# ip_phone_e_wifi.net
KiCad netlist of a schematic drawn in Altium Designer
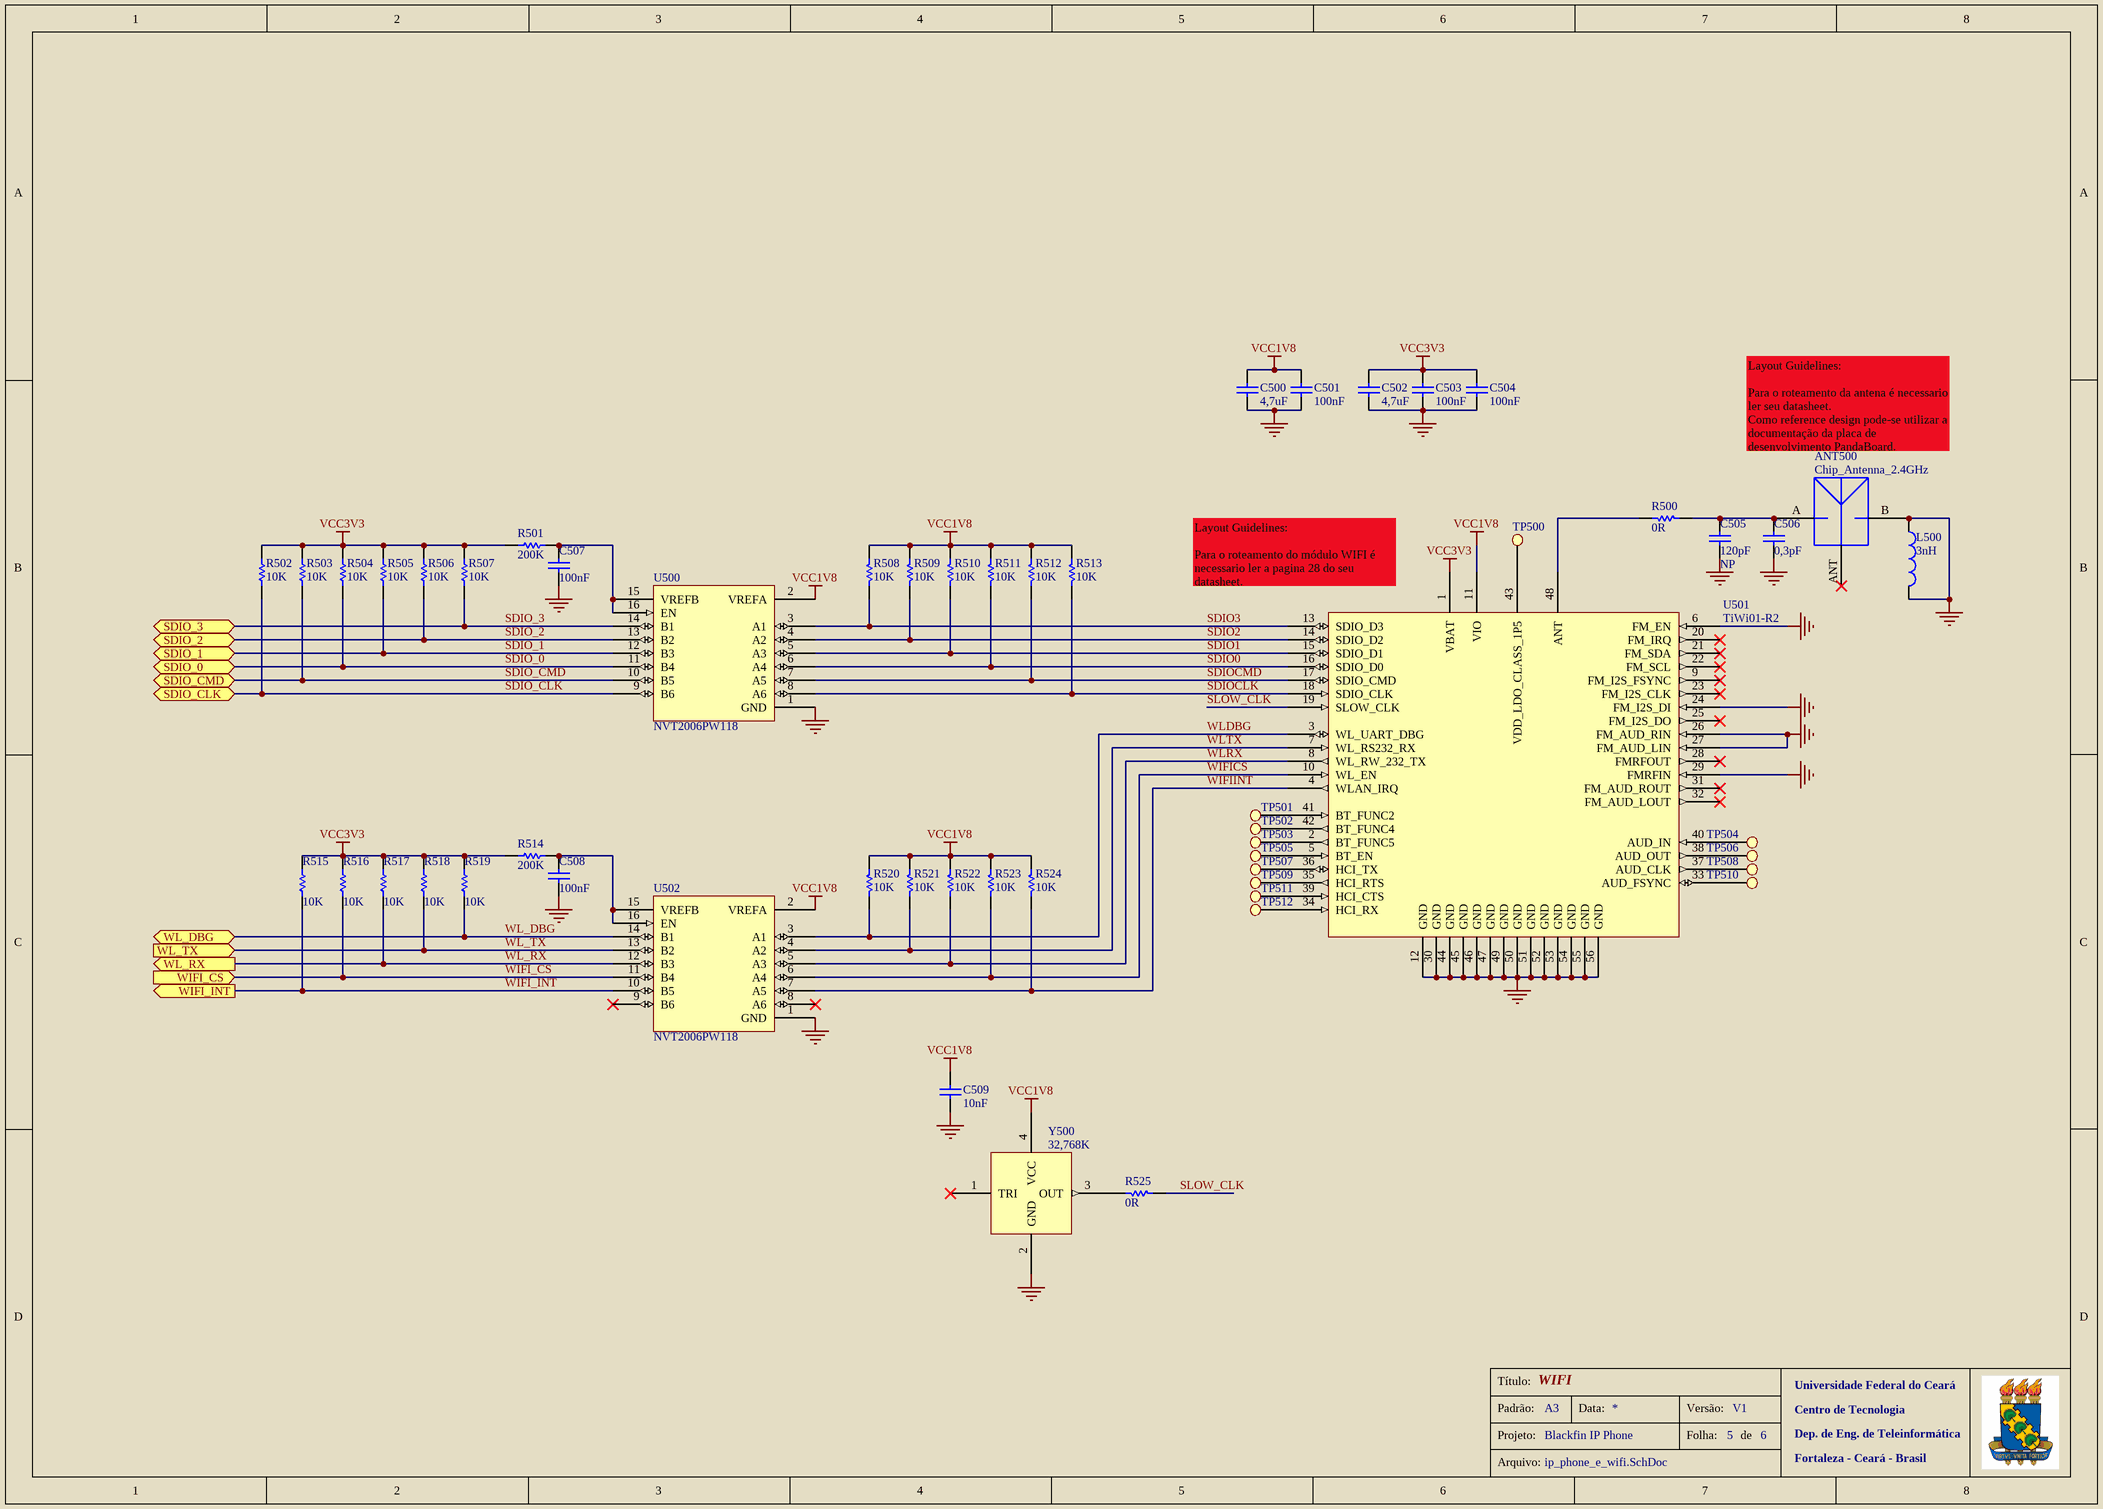
[diagram p0: ip_phone_e_wifi.SchDoc]

(export (version "E")
  (design (tool "Eeschema 10.0.6"))
  (components
    (comp (ref "ANT500")
      (value "Chip_Antenna_2.4GHz")
      (footprint "ip_phone:ANTENNA")
      (description "Antenna 2.4GHz Ceramic Chip SMD")
      (fields (field (name "MANUFACTURER") "TDK") (field (name "EVENDORPART#") "445-6134-1-ND"))
      (libsource (lib "ip_phone") (part "Antenna2_4GHzChip"))
    )
    (comp (ref "C500")
      (value "4,7uF")
      (footprint "ip_phone:CC1005-0402")
      (description "MLCC - SMD/SMT 4.7uF 20% 6.3Volts 0402")
      (fields (field (name "EVENDORPART#") "810-C1005X5R0J475M") (field (name "MANUFACTURER") "TDK"))
      (libsource (lib "ip_phone") (part "Capacitor"))
    )
    (comp (ref "C501")
      (value "100nF")
      (footprint "ip_phone:CC1005-0402")
      (description "MLCC - SMD/SMT 0.1UF 16V 10% 0402")
      (fields (field (name "EVENDORPART#") "810-C1005X7R1C104K") (field (name "MANUFACTURER") "TDK"))
      (libsource (lib "ip_phone") (part "Capacitor"))
    )
    (comp (ref "C502")
      (value "4,7uF")
      (footprint "ip_phone:CC1005-0402")
      (description "MLCC - SMD/SMT 4.7uF 20% 6.3Volts 0402")
      (fields (field (name "EVENDORPART#") "810-C1005X5R0J475M") (field (name "MANUFACTURER") "TDK"))
      (libsource (lib "ip_phone") (part "Capacitor"))
    )
    (comp (ref "C503")
      (value "100nF")
      (footprint "ip_phone:CC1005-0402")
      (description "MLCC - SMD/SMT 0.1UF 16V 10% 0402")
      (fields (field (name "EVENDORPART#") "810-C1005X7R1C104K") (field (name "MANUFACTURER") "TDK"))
      (libsource (lib "ip_phone") (part "Capacitor"))
    )
    (comp (ref "C504")
      (value "100nF")
      (footprint "ip_phone:CC1005-0402")
      (description "MLCC - SMD/SMT 0.1UF 16V 10% 0402")
      (fields (field (name "EVENDORPART#") "810-C1005X7R1C104K") (field (name "MANUFACTURER") "TDK"))
      (libsource (lib "ip_phone") (part "Capacitor"))
    )
    (comp (ref "C505")
      (value "120pF")
      (footprint "ip_phone:CC1005-0402_NP")
      (description "MLCC - SMD/SMT 0402 120pF 50volts C0G 5%")
      (fields
        (field (name "EVENDORPART#") "810-C1005C0G1H121J")
        (field (name "MANUFACTURER") "TDK")
        (field (name "NP") "NP")
      )
      (libsource (lib "ip_phone") (part "Capacitor"))
    )
    (comp (ref "C506")
      (value "0,3pF")
      (footprint "ip_phone:CC1005-0402")
      (description "MLCC - SMD/SMT 0.3pF 50Volts C0G 0.1pF")
      (fields (field (name "EVENDORPART#") "81-GRM1535C1HR30BD5D") (field (name "MANUFACTURER") "Murata"))
      (libsource (lib "ip_phone") (part "Capacitor"))
    )
    (comp (ref "C507")
      (value "100nF")
      (footprint "ip_phone:CC1005-0402")
      (description "MLCC - SMD/SMT 0.1UF 16V 10% 0402")
      (fields (field (name "EVENDORPART#") "810-C1005X7R1C104K") (field (name "MANUFACTURER") "TDK"))
      (libsource (lib "ip_phone") (part "Capacitor"))
    )
    (comp (ref "C508")
      (value "100nF")
      (footprint "ip_phone:CC1005-0402")
      (description "MLCC - SMD/SMT 0.1UF 16V 10% 0402")
      (fields (field (name "EVENDORPART#") "810-C1005X7R1C104K") (field (name "MANUFACTURER") "TDK"))
      (libsource (lib "ip_phone") (part "Capacitor"))
    )
    (comp (ref "C509")
      (value "10nF")
      (footprint "ip_phone:CC1005-0402")
      (description "Ceramic Capacitor 10nF 50V X7R 0402")
      (fields (field (name "EVENDORPART#") "810-C1005X7R1C103K") (field (name "MANUFACTURER") "TDK"))
      (libsource (lib "ip_phone") (part "Capacitor"))
    )
    (comp (ref "L500")
      (value "3nH")
      (footprint "ip_phone:INDUTOR_0402")
      (description "Inductor")
      (fields
        (field (name "EVENDORPART#") "712-1457-1-ND")
        (field (name "MANUFACTURER") "Johanson Technology Inc")
      )
      (libsource (lib "ip_phone") (part "Inductor"))
    )
    (comp (ref "R500")
      (value "0R")
      (footprint "ip_phone:CR1005-0402")
      (description "Thick Film Resistors 0402 1/16W Jumper")
      (fields
        (field (name "EVENDORPART#") "667-ERJ-2GE0R00X")
        (field (name "MANUFACTURER") "Panasonic Electronic Components")
      )
      (libsource (lib "ip_phone") (part "Resistor"))
    )
    (comp (ref "R501")
      (value "200K")
      (footprint "ip_phone:CR1005-0402")
      (description "Thick Film Resistors 1/16WATT 200K 0402")
      (fields (field (name "EVENDORPART#") "304-200K-RC") (field (name "MANUFACTURER") "Xicon"))
      (libsource (lib "ip_phone") (part "Resistor"))
    )
    (comp (ref "R502")
      (value "10K")
      (footprint "ip_phone:CR1005-0402")
      (description "Thick Film Resistors SMD 0402 10K 5%  1/16 W")
      (fields (field (name "EVENDORPART#") "311-10KJRCT-ND") (field (name "MANUFACTURER") "Yageo"))
      (libsource (lib "ip_phone") (part "Resistor"))
    )
    (comp (ref "R503")
      (value "10K")
      (footprint "ip_phone:CR1005-0402")
      (description "Thick Film Resistors SMD 0402 10K 5%  1/16 W")
      (fields (field (name "EVENDORPART#") "311-10KJRCT-ND") (field (name "MANUFACTURER") "Yageo"))
      (libsource (lib "ip_phone") (part "Resistor"))
    )
    (comp (ref "R504")
      (value "10K")
      (footprint "ip_phone:CR1005-0402")
      (description "Thick Film Resistors SMD 0402 10K 5%  1/16 W")
      (fields (field (name "EVENDORPART#") "311-10KJRCT-ND") (field (name "MANUFACTURER") "Yageo"))
      (libsource (lib "ip_phone") (part "Resistor"))
    )
    (comp (ref "R505")
      (value "10K")
      (footprint "ip_phone:CR1005-0402")
      (description "Thick Film Resistors SMD 0402 10K 5%  1/16 W")
      (fields (field (name "EVENDORPART#") "311-10KJRCT-ND") (field (name "MANUFACTURER") "Yageo"))
      (libsource (lib "ip_phone") (part "Resistor"))
    )
    (comp (ref "R506")
      (value "10K")
      (footprint "ip_phone:CR1005-0402")
      (description "Thick Film Resistors SMD 0402 10K 5%  1/16 W")
      (fields (field (name "EVENDORPART#") "311-10KJRCT-ND") (field (name "MANUFACTURER") "Yageo"))
      (libsource (lib "ip_phone") (part "Resistor"))
    )
    (comp (ref "R507")
      (value "10K")
      (footprint "ip_phone:CR1005-0402")
      (description "Thick Film Resistors SMD 0402 10K 5%  1/16 W")
      (fields (field (name "EVENDORPART#") "311-10KJRCT-ND") (field (name "MANUFACTURER") "Yageo"))
      (libsource (lib "ip_phone") (part "Resistor"))
    )
    (comp (ref "R508")
      (value "10K")
      (footprint "ip_phone:CR1005-0402")
      (description "Thick Film Resistors SMD 0402 10K 5%  1/16 W")
      (fields (field (name "EVENDORPART#") "311-10KJRCT-ND") (field (name "MANUFACTURER") "Yageo"))
      (libsource (lib "ip_phone") (part "Resistor"))
    )
    (comp (ref "R509")
      (value "10K")
      (footprint "ip_phone:CR1005-0402")
      (description "Thick Film Resistors SMD 0402 10K 5%  1/16 W")
      (fields (field (name "EVENDORPART#") "311-10KJRCT-ND") (field (name "MANUFACTURER") "Yageo"))
      (libsource (lib "ip_phone") (part "Resistor"))
    )
    (comp (ref "R510")
      (value "10K")
      (footprint "ip_phone:CR1005-0402")
      (description "Thick Film Resistors SMD 0402 10K 5%  1/16 W")
      (fields (field (name "EVENDORPART#") "311-10KJRCT-ND") (field (name "MANUFACTURER") "Yageo"))
      (libsource (lib "ip_phone") (part "Resistor"))
    )
    (comp (ref "R511")
      (value "10K")
      (footprint "ip_phone:CR1005-0402")
      (description "Thick Film Resistors SMD 0402 10K 5%  1/16 W")
      (fields (field (name "EVENDORPART#") "311-10KJRCT-ND") (field (name "MANUFACTURER") "Yageo"))
      (libsource (lib "ip_phone") (part "Resistor"))
    )
    (comp (ref "R512")
      (value "10K")
      (footprint "ip_phone:CR1005-0402")
      (description "Thick Film Resistors SMD 0402 10K 5%  1/16 W")
      (fields (field (name "EVENDORPART#") "311-10KJRCT-ND") (field (name "MANUFACTURER") "Yageo"))
      (libsource (lib "ip_phone") (part "Resistor"))
    )
    (comp (ref "R513")
      (value "10K")
      (footprint "ip_phone:CR1005-0402")
      (description "Thick Film Resistors SMD 0402 10K 5%  1/16 W")
      (fields (field (name "EVENDORPART#") "311-10KJRCT-ND") (field (name "MANUFACTURER") "Yageo"))
      (libsource (lib "ip_phone") (part "Resistor"))
    )
    (comp (ref "R514")
      (value "200K")
      (footprint "ip_phone:CR1005-0402")
      (description "Thick Film Resistors 1/16WATT 200K 0402")
      (fields (field (name "EVENDORPART#") "304-200K-RC") (field (name "MANUFACTURER") "Xicon"))
      (libsource (lib "ip_phone") (part "Resistor"))
    )
    (comp (ref "R515")
      (value "10K")
      (footprint "ip_phone:CR1005-0402")
      (description "Thick Film Resistors SMD 0402 10K 5%  1/16 W")
      (fields (field (name "EVENDORPART#") "311-10KJRCT-ND") (field (name "MANUFACTURER") "Yageo"))
      (libsource (lib "ip_phone") (part "Resistor"))
    )
    (comp (ref "R516")
      (value "10K")
      (footprint "ip_phone:CR1005-0402")
      (description "Thick Film Resistors SMD 0402 10K 5%  1/16 W")
      (fields (field (name "EVENDORPART#") "311-10KJRCT-ND") (field (name "MANUFACTURER") "Yageo"))
      (libsource (lib "ip_phone") (part "Resistor"))
    )
    (comp (ref "R517")
      (value "10K")
      (footprint "ip_phone:CR1005-0402")
      (description "Thick Film Resistors SMD 0402 10K 5%  1/16 W")
      (fields (field (name "EVENDORPART#") "311-10KJRCT-ND") (field (name "MANUFACTURER") "Yageo"))
      (libsource (lib "ip_phone") (part "Resistor"))
    )
    (comp (ref "R518")
      (value "10K")
      (footprint "ip_phone:CR1005-0402")
      (description "Thick Film Resistors SMD 0402 10K 5%  1/16 W")
      (fields (field (name "EVENDORPART#") "311-10KJRCT-ND") (field (name "MANUFACTURER") "Yageo"))
      (libsource (lib "ip_phone") (part "Resistor"))
    )
    (comp (ref "R519")
      (value "10K")
      (footprint "ip_phone:CR1005-0402")
      (description "Thick Film Resistors SMD 0402 10K 5%  1/16 W")
      (fields (field (name "EVENDORPART#") "311-10KJRCT-ND") (field (name "MANUFACTURER") "Yageo"))
      (libsource (lib "ip_phone") (part "Resistor"))
    )
    (comp (ref "R520")
      (value "10K")
      (footprint "ip_phone:CR1005-0402")
      (description "Thick Film Resistors SMD 0402 10K 5%  1/16 W")
      (fields (field (name "EVENDORPART#") "311-10KJRCT-ND") (field (name "MANUFACTURER") "Yageo"))
      (libsource (lib "ip_phone") (part "Resistor"))
    )
    (comp (ref "R521")
      (value "10K")
      (footprint "ip_phone:CR1005-0402")
      (description "Thick Film Resistors SMD 0402 10K 5%  1/16 W")
      (fields (field (name "EVENDORPART#") "311-10KJRCT-ND") (field (name "MANUFACTURER") "Yageo"))
      (libsource (lib "ip_phone") (part "Resistor"))
    )
    (comp (ref "R522")
      (value "10K")
      (footprint "ip_phone:CR1005-0402")
      (description "Thick Film Resistors SMD 0402 10K 5%  1/16 W")
      (fields (field (name "EVENDORPART#") "311-10KJRCT-ND") (field (name "MANUFACTURER") "Yageo"))
      (libsource (lib "ip_phone") (part "Resistor"))
    )
    (comp (ref "R523")
      (value "10K")
      (footprint "ip_phone:CR1005-0402")
      (description "Thick Film Resistors SMD 0402 10K 5%  1/16 W")
      (fields (field (name "EVENDORPART#") "311-10KJRCT-ND") (field (name "MANUFACTURER") "Yageo"))
      (libsource (lib "ip_phone") (part "Resistor"))
    )
    (comp (ref "R524")
      (value "10K")
      (footprint "ip_phone:CR1005-0402")
      (description "Thick Film Resistors SMD 0402 10K 5%  1/16 W")
      (fields (field (name "EVENDORPART#") "311-10KJRCT-ND") (field (name "MANUFACTURER") "Yageo"))
      (libsource (lib "ip_phone") (part "Resistor"))
    )
    (comp (ref "R525")
      (value "0R")
      (footprint "ip_phone:CR1005-0402")
      (description "Thick Film Resistors 0402 1/16W Jumper")
      (fields
        (field (name "EVENDORPART#") "667-ERJ-2GE0R00X")
        (field (name "MANUFACTURER") "Panasonic Electronic Components")
      )
      (libsource (lib "ip_phone") (part "Resistor"))
    )
    (comp (ref "TP500")
      (value "Test Point")
      (footprint "ip_phone:Test Point")
      (fields (field (name "EVENDORPART#") "NÃO SE APLICA"))
      (libsource (lib "ip_phone") (part "Test Point"))
    )
    (comp (ref "TP501")
      (value "Test Point")
      (footprint "ip_phone:Test Point")
      (fields (field (name "EVENDORPART#") "NÃO SE APLICA"))
      (libsource (lib "ip_phone") (part "Test Point"))
    )
    (comp (ref "TP502")
      (value "Test Point")
      (footprint "ip_phone:Test Point")
      (fields (field (name "EVENDORPART#") "NÃO SE APLICA"))
      (libsource (lib "ip_phone") (part "Test Point"))
    )
    (comp (ref "TP503")
      (value "Test Point")
      (footprint "ip_phone:Test Point")
      (fields (field (name "EVENDORPART#") "NÃO SE APLICA"))
      (libsource (lib "ip_phone") (part "Test Point"))
    )
    (comp (ref "TP504")
      (value "Test Point")
      (footprint "ip_phone:Test Point")
      (fields (field (name "EVENDORPART#") "NÃO SE APLICA"))
      (libsource (lib "ip_phone") (part "Test Point"))
    )
    (comp (ref "TP505")
      (value "Test Point")
      (footprint "ip_phone:Test Point")
      (fields (field (name "EVENDORPART#") "NÃO SE APLICA"))
      (libsource (lib "ip_phone") (part "Test Point"))
    )
    (comp (ref "TP506")
      (value "Test Point")
      (footprint "ip_phone:Test Point")
      (fields (field (name "EVENDORPART#") "NÃO SE APLICA"))
      (libsource (lib "ip_phone") (part "Test Point"))
    )
    (comp (ref "TP507")
      (value "Test Point")
      (footprint "ip_phone:Test Point")
      (fields (field (name "EVENDORPART#") "NÃO SE APLICA"))
      (libsource (lib "ip_phone") (part "Test Point"))
    )
    (comp (ref "TP508")
      (value "Test Point")
      (footprint "ip_phone:Test Point")
      (fields (field (name "EVENDORPART#") "NÃO SE APLICA"))
      (libsource (lib "ip_phone") (part "Test Point"))
    )
    (comp (ref "TP509")
      (value "Test Point")
      (footprint "ip_phone:Test Point")
      (fields (field (name "EVENDORPART#") "NÃO SE APLICA"))
      (libsource (lib "ip_phone") (part "Test Point"))
    )
    (comp (ref "TP510")
      (value "Test Point")
      (footprint "ip_phone:Test Point")
      (fields (field (name "EVENDORPART#") "NÃO SE APLICA"))
      (libsource (lib "ip_phone") (part "Test Point"))
    )
    (comp (ref "TP511")
      (value "Test Point")
      (footprint "ip_phone:Test Point")
      (fields (field (name "EVENDORPART#") "NÃO SE APLICA"))
      (libsource (lib "ip_phone") (part "Test Point"))
    )
    (comp (ref "TP512")
      (value "Test Point")
      (footprint "ip_phone:Test Point")
      (fields (field (name "EVENDORPART#") "NÃO SE APLICA"))
      (libsource (lib "ip_phone") (part "Test Point"))
    )
    (comp (ref "U500")
      (value "NVT2006PW118")
      (footprint "ip_phone:TSSOP16")
      (description "Translation - Voltage Levels +/-50mA 1.5ns 2.1-5V")
      (fields
        (field (name "EVENDORPART#") "771-NVT2006PW118")
        (field (name "MANUFACTURER") "NXP Semiconductors")
      )
      (libsource (lib "ip_phone") (part "NVT2006PW118"))
    )
    (comp (ref "U501")
      (value "TiWi01-R2")
      (footprint "ip_phone:WIFI_MODULE")
      (description "WiFi / 802.11 TiWi01-R2 Module with U.FL Connector")
      (fields (field (name "EVENDORPART#") "741-450-0037") (field (name "MANUFACTURER") "LS Research"))
      (libsource (lib "ip_phone") (part "TiWi01-R2"))
    )
    (comp (ref "U502")
      (value "NVT2006PW118")
      (footprint "ip_phone:TSSOP16")
      (description "Translation - Voltage Levels +/-50mA 1.5ns 2.1-5V")
      (fields
        (field (name "EVENDORPART#") "771-NVT2006PW118")
        (field (name "MANUFACTURER") "NXP Semiconductors")
      )
      (libsource (lib "ip_phone") (part "NVT2006PW118"))
    )
    (comp (ref "Y500")
      (value "32,768K")
      (footprint "ip_phone:OSCILLATOR_32K")
      (description "Standard Clock Oscillators 32.768KHz 1.8V -40C +85C 25ppm")
      (fields (field (name "EVENDORPART#") "815-ASEK2-32.7K-LRT") (field (name "MANUFACTURER") "Abracon"))
      (libsource (lib "ip_phone") (part "Oscillator_32K"))
    )
  )
  (nets
    (net (code "1") (name "/SDIO0") (class "Default")
      (node (ref "R511") (pin "1") (pinfunction "1_1") (pintype "passive"))
      (node (ref "U500") (pin "6") (pinfunction "A4_6") (pintype "bidirectional"))
      (node (ref "U501") (pin "16") (pinfunction "SDIO_D0_16") (pintype "bidirectional"))
    )
    (net (code "2") (name "/SDIO1") (class "Default")
      (node (ref "R510") (pin "1") (pinfunction "1_1") (pintype "passive"))
      (node (ref "U500") (pin "5") (pinfunction "A3_5") (pintype "bidirectional"))
      (node (ref "U501") (pin "15") (pinfunction "SDIO_D1_15") (pintype "bidirectional"))
    )
    (net (code "3") (name "/SDIO2") (class "Default")
      (node (ref "R509") (pin "1") (pinfunction "1_1") (pintype "passive"))
      (node (ref "U500") (pin "4") (pinfunction "A2_4") (pintype "bidirectional"))
      (node (ref "U501") (pin "14") (pinfunction "SDIO_D2_14") (pintype "bidirectional"))
    )
    (net (code "4") (name "/SDIO3") (class "Default")
      (node (ref "R508") (pin "1") (pinfunction "1_1") (pintype "passive"))
      (node (ref "U500") (pin "3") (pinfunction "A1_3") (pintype "bidirectional"))
      (node (ref "U501") (pin "13") (pinfunction "SDIO_D3_13") (pintype "bidirectional"))
    )
    (net (code "5") (name "/SDIOCLK") (class "Default")
      (node (ref "R513") (pin "1") (pinfunction "1_1") (pintype "passive"))
      (node (ref "U500") (pin "8") (pinfunction "A6_8") (pintype "bidirectional"))
      (node (ref "U501") (pin "18") (pinfunction "SDIO_CLK_18") (pintype "input"))
    )
    (net (code "6") (name "/SDIOCMD") (class "Default")
      (node (ref "R512") (pin "1") (pinfunction "1_1") (pintype "passive"))
      (node (ref "U500") (pin "7") (pinfunction "A5_7") (pintype "bidirectional"))
      (node (ref "U501") (pin "17") (pinfunction "SDIO_CMD_17") (pintype "bidirectional"))
    )
    (net (code "7") (name "/SDIO_0") (class "Default")
      (node (ref "R504") (pin "2") (pinfunction "2_2") (pintype "passive"))
      (node (ref "U500") (pin "11") (pinfunction "B4_11") (pintype "bidirectional"))
    )
    (net (code "8") (name "/SDIO_1") (class "Default")
      (node (ref "R505") (pin "2") (pinfunction "2_2") (pintype "passive"))
      (node (ref "U500") (pin "12") (pinfunction "B3_12") (pintype "bidirectional"))
    )
    (net (code "9") (name "/SDIO_2") (class "Default")
      (node (ref "R506") (pin "2") (pinfunction "2_2") (pintype "passive"))
      (node (ref "U500") (pin "13") (pinfunction "B2_13") (pintype "bidirectional"))
    )
    (net (code "10") (name "/SDIO_3") (class "Default")
      (node (ref "R507") (pin "2") (pinfunction "2_2") (pintype "passive"))
      (node (ref "U500") (pin "14") (pinfunction "B1_14") (pintype "bidirectional"))
    )
    (net (code "11") (name "/SDIO_CLK") (class "Default")
      (node (ref "R502") (pin "2") (pinfunction "2_2") (pintype "passive"))
      (node (ref "U500") (pin "9") (pinfunction "B6_9") (pintype "bidirectional"))
    )
    (net (code "12") (name "/SDIO_CMD") (class "Default")
      (node (ref "R503") (pin "2") (pinfunction "2_2") (pintype "passive"))
      (node (ref "U500") (pin "10") (pinfunction "B5_10") (pintype "bidirectional"))
    )
    (net (code "13") (name "/SLOW_CLK") (class "Default")
      (node (ref "R525") (pin "1") (pinfunction "1_1") (pintype "passive"))
      (node (ref "U501") (pin "19") (pinfunction "SLOW_CLK_19") (pintype "input"))
    )
    (net (code "14") (name "/WIFICS") (class "Default")
      (node (ref "R523") (pin "1") (pinfunction "1_1") (pintype "passive"))
      (node (ref "U501") (pin "10") (pinfunction "WL_EN_10") (pintype "input"))
      (node (ref "U502") (pin "6") (pinfunction "A4_6") (pintype "bidirectional"))
    )
    (net (code "15") (name "/WIFIINT") (class "Default")
      (node (ref "R524") (pin "1") (pinfunction "1_1") (pintype "passive"))
      (node (ref "U501") (pin "4") (pinfunction "WLAN_IRQ_4") (pintype "output"))
      (node (ref "U502") (pin "7") (pinfunction "A5_7") (pintype "bidirectional"))
    )
    (net (code "16") (name "/WIFI_CS") (class "Default")
      (node (ref "R516") (pin "1") (pinfunction "1_1") (pintype "passive"))
      (node (ref "U502") (pin "11") (pinfunction "B4_11") (pintype "bidirectional"))
    )
    (net (code "17") (name "/WIFI_INT") (class "Default")
      (node (ref "R515") (pin "1") (pinfunction "1_1") (pintype "passive"))
      (node (ref "U502") (pin "10") (pinfunction "B5_10") (pintype "bidirectional"))
    )
    (net (code "18") (name "/WLDBG") (class "Default")
      (node (ref "R520") (pin "1") (pinfunction "1_1") (pintype "passive"))
      (node (ref "U501") (pin "3") (pinfunction "WL_UART_DBG_3") (pintype "bidirectional"))
      (node (ref "U502") (pin "3") (pinfunction "A1_3") (pintype "bidirectional"))
    )
    (net (code "19") (name "/WLRX") (class "Default")
      (node (ref "R522") (pin "1") (pinfunction "1_1") (pintype "passive"))
      (node (ref "U501") (pin "8") (pinfunction "WL_RW_232_TX_8") (pintype "output"))
      (node (ref "U502") (pin "5") (pinfunction "A3_5") (pintype "bidirectional"))
    )
    (net (code "20") (name "/WLTX") (class "Default")
      (node (ref "R521") (pin "1") (pinfunction "1_1") (pintype "passive"))
      (node (ref "U501") (pin "7") (pinfunction "WL_RS232_RX_7") (pintype "input"))
      (node (ref "U502") (pin "4") (pinfunction "A2_4") (pintype "bidirectional"))
    )
    (net (code "21") (name "/WL_DBG") (class "Default")
      (node (ref "R519") (pin "1") (pinfunction "1_1") (pintype "passive"))
      (node (ref "U502") (pin "14") (pinfunction "B1_14") (pintype "bidirectional"))
    )
    (net (code "22") (name "/WL_RX") (class "Default")
      (node (ref "R517") (pin "1") (pinfunction "1_1") (pintype "passive"))
      (node (ref "U502") (pin "12") (pinfunction "B3_12") (pintype "bidirectional"))
    )
    (net (code "23") (name "/WL_TX") (class "Default")
      (node (ref "R518") (pin "1") (pinfunction "1_1") (pintype "passive"))
      (node (ref "U502") (pin "13") (pinfunction "B2_13") (pintype "bidirectional"))
    )
    (net (code "24") (name "GND") (class "Default")
      (node (ref "ANT500") (pin "B") (pinfunction "FIXINGELEC_B") (pintype "passive"))
      (node (ref "C500") (pin "2") (pinfunction "2_2") (pintype "passive"))
      (node (ref "C501") (pin "2") (pinfunction "2_2") (pintype "passive"))
      (node (ref "C502") (pin "2") (pinfunction "2_2") (pintype "passive"))
      (node (ref "C503") (pin "2") (pinfunction "2_2") (pintype "passive"))
      (node (ref "C504") (pin "2") (pinfunction "2_2") (pintype "passive"))
      (node (ref "C505") (pin "1") (pinfunction "1_1") (pintype "passive"))
      (node (ref "C506") (pin "1") (pinfunction "1_1") (pintype "passive"))
      (node (ref "C507") (pin "1") (pinfunction "1_1") (pintype "passive"))
      (node (ref "C508") (pin "1") (pinfunction "1_1") (pintype "passive"))
      (node (ref "C509") (pin "1") (pinfunction "1_1") (pintype "passive"))
      (node (ref "L500") (pin "1") (pinfunction "1_1") (pintype "passive"))
      (node (ref "L500") (pin "2") (pinfunction "2_2") (pintype "passive"))
      (node (ref "U500") (pin "1") (pinfunction "GND_1") (pintype "power_in"))
      (node (ref "U501") (pin "12") (pinfunction "GND_12") (pintype "power_in"))
      (node (ref "U501") (pin "24") (pinfunction "FM_I2S_DI_24") (pintype "input"))
      (node (ref "U501") (pin "26") (pinfunction "FM_AUD_RIN_26") (pintype "input"))
      (node (ref "U501") (pin "27") (pinfunction "FM_AUD_LIN_27") (pintype "input"))
      (node (ref "U501") (pin "29") (pinfunction "FMRFIN_29") (pintype "input"))
      (node (ref "U501") (pin "30") (pinfunction "GND_30") (pintype "power_in"))
      (node (ref "U501") (pin "44") (pinfunction "GND_44") (pintype "power_in"))
      (node (ref "U501") (pin "45") (pinfunction "GND_45") (pintype "power_in"))
      (node (ref "U501") (pin "46") (pinfunction "GND_46") (pintype "power_in"))
      (node (ref "U501") (pin "47") (pinfunction "GND_47") (pintype "power_in"))
      (node (ref "U501") (pin "49") (pinfunction "GND_49") (pintype "power_in"))
      (node (ref "U501") (pin "50") (pinfunction "GND_50") (pintype "power_in"))
      (node (ref "U501") (pin "51") (pinfunction "GND_51") (pintype "power_in"))
      (node (ref "U501") (pin "52") (pinfunction "GND_52") (pintype "power_in"))
      (node (ref "U501") (pin "53") (pinfunction "GND_53") (pintype "power_in"))
      (node (ref "U501") (pin "54") (pinfunction "GND_54") (pintype "power_in"))
      (node (ref "U501") (pin "55") (pinfunction "GND_55") (pintype "power_in"))
      (node (ref "U501") (pin "56") (pinfunction "GND_56") (pintype "power_in"))
      (node (ref "U501") (pin "6") (pinfunction "FM_EN_6") (pintype "input"))
      (node (ref "U502") (pin "1") (pinfunction "GND_1") (pintype "power_in"))
      (node (ref "Y500") (pin "2") (pinfunction "GND_2") (pintype "power_in"))
    )
    (net (code "25") (name "Net-(ANT500-FEEDPOINT)") (class "Default")
      (node (ref "ANT500") (pin "A") (pinfunction "FEEDPOINT_A") (pintype "passive"))
      (node (ref "C505") (pin "2") (pinfunction "2_2") (pintype "passive"))
      (node (ref "C506") (pin "2") (pinfunction "2_2") (pintype "passive"))
      (node (ref "R500") (pin "1") (pinfunction "1_1") (pintype "passive"))
    )
    (net (code "26") (name "Net-(U500-EN)") (class "Default")
      (node (ref "C507") (pin "2") (pinfunction "2_2") (pintype "passive"))
      (node (ref "R501") (pin "1") (pinfunction "1_1") (pintype "passive"))
      (node (ref "U500") (pin "15") (pinfunction "VREFB_15") (pintype "power_in"))
      (node (ref "U500") (pin "16") (pinfunction "EN_16") (pintype "input"))
    )
    (net (code "27") (name "Net-(U501-ANT)") (class "Default")
      (node (ref "R500") (pin "2") (pinfunction "2_2") (pintype "passive"))
      (node (ref "U501") (pin "48") (pinfunction "ANT_48") (pintype "passive"))
    )
    (net (code "28") (name "Net-(U501-AUD_CLK)") (class "Default")
      (node (ref "TP508") (pin "1") (pinfunction "1_1") (pintype "passive"))
      (node (ref "U501") (pin "37") (pinfunction "AUD_CLK_37") (pintype "output"))
    )
    (net (code "29") (name "Net-(U501-AUD_FSYNC)") (class "Default")
      (node (ref "TP510") (pin "1") (pinfunction "1_1") (pintype "passive"))
      (node (ref "U501") (pin "33") (pinfunction "AUD_FSYNC_33") (pintype "bidirectional"))
    )
    (net (code "30") (name "Net-(U501-AUD_IN)") (class "Default")
      (node (ref "TP504") (pin "1") (pinfunction "1_1") (pintype "passive"))
      (node (ref "U501") (pin "40") (pinfunction "AUD_IN_40") (pintype "input"))
    )
    (net (code "31") (name "Net-(U501-AUD_OUT)") (class "Default")
      (node (ref "TP506") (pin "1") (pinfunction "1_1") (pintype "passive"))
      (node (ref "U501") (pin "38") (pinfunction "AUD_OUT_38") (pintype "output"))
    )
    (net (code "32") (name "Net-(U501-BT_EN)") (class "Default")
      (node (ref "TP505") (pin "1") (pinfunction "1_1") (pintype "passive"))
      (node (ref "U501") (pin "5") (pinfunction "BT_EN_5") (pintype "input"))
    )
    (net (code "33") (name "Net-(U501-BT_FUNC2)") (class "Default")
      (node (ref "TP501") (pin "1") (pinfunction "1_1") (pintype "passive"))
      (node (ref "U501") (pin "41") (pinfunction "BT_FUNC2_41") (pintype "input"))
    )
    (net (code "34") (name "Net-(U501-BT_FUNC4)") (class "Default")
      (node (ref "TP502") (pin "1") (pinfunction "1_1") (pintype "passive"))
      (node (ref "U501") (pin "42") (pinfunction "BT_FUNC4_42") (pintype "output"))
    )
    (net (code "35") (name "Net-(U501-BT_FUNC5)") (class "Default")
      (node (ref "TP503") (pin "1") (pinfunction "1_1") (pintype "passive"))
      (node (ref "U501") (pin "2") (pinfunction "BT_FUNC5_2") (pintype "output"))
    )
    (net (code "36") (name "Net-(U501-HCI_CTS)") (class "Default")
      (node (ref "TP511") (pin "1") (pinfunction "1_1") (pintype "passive"))
      (node (ref "U501") (pin "39") (pinfunction "HCI_CTS_39") (pintype "input"))
    )
    (net (code "37") (name "Net-(U501-HCI_RTS)") (class "Default")
      (node (ref "TP509") (pin "1") (pinfunction "1_1") (pintype "passive"))
      (node (ref "U501") (pin "35") (pinfunction "HCI_RTS_35") (pintype "output"))
    )
    (net (code "38") (name "Net-(U501-HCI_RX)") (class "Default")
      (node (ref "TP512") (pin "1") (pinfunction "1_1") (pintype "passive"))
      (node (ref "U501") (pin "34") (pinfunction "HCI_RX_34") (pintype "input"))
    )
    (net (code "39") (name "Net-(U501-HCI_TX)") (class "Default")
      (node (ref "TP507") (pin "1") (pinfunction "1_1") (pintype "passive"))
      (node (ref "U501") (pin "36") (pinfunction "HCI_TX_36") (pintype "bidirectional"))
    )
    (net (code "40") (name "Net-(U501-VDD_LDO_CLASS_1P5)") (class "Default")
      (node (ref "TP500") (pin "1") (pinfunction "1_1") (pintype "passive"))
      (node (ref "U501") (pin "43") (pinfunction "VDD_LDO_CLASS_1P5_43") (pintype "passive"))
    )
    (net (code "41") (name "Net-(U502-EN)") (class "Default")
      (node (ref "C508") (pin "2") (pinfunction "2_2") (pintype "passive"))
      (node (ref "R514") (pin "1") (pinfunction "1_1") (pintype "passive"))
      (node (ref "U502") (pin "15") (pinfunction "VREFB_15") (pintype "power_in"))
      (node (ref "U502") (pin "16") (pinfunction "EN_16") (pintype "input"))
    )
    (net (code "42") (name "Net-(Y500-OUT)") (class "Default")
      (node (ref "R525") (pin "2") (pinfunction "2_2") (pintype "passive"))
      (node (ref "Y500") (pin "3") (pinfunction "OUT_3") (pintype "output"))
    )
    (net (code "43") (name "VCC1V8") (class "Default")
      (node (ref "C500") (pin "1") (pinfunction "1_1") (pintype "passive"))
      (node (ref "C501") (pin "1") (pinfunction "1_1") (pintype "passive"))
      (node (ref "C509") (pin "2") (pinfunction "2_2") (pintype "passive"))
      (node (ref "R508") (pin "2") (pinfunction "2_2") (pintype "passive"))
      (node (ref "R509") (pin "2") (pinfunction "2_2") (pintype "passive"))
      (node (ref "R510") (pin "2") (pinfunction "2_2") (pintype "passive"))
      (node (ref "R511") (pin "2") (pinfunction "2_2") (pintype "passive"))
      (node (ref "R512") (pin "2") (pinfunction "2_2") (pintype "passive"))
      (node (ref "R513") (pin "2") (pinfunction "2_2") (pintype "passive"))
      (node (ref "R520") (pin "2") (pinfunction "2_2") (pintype "passive"))
      (node (ref "R521") (pin "2") (pinfunction "2_2") (pintype "passive"))
      (node (ref "R522") (pin "2") (pinfunction "2_2") (pintype "passive"))
      (node (ref "R523") (pin "2") (pinfunction "2_2") (pintype "passive"))
      (node (ref "R524") (pin "2") (pinfunction "2_2") (pintype "passive"))
      (node (ref "U500") (pin "2") (pinfunction "VREFA_2") (pintype "power_in"))
      (node (ref "U501") (pin "11") (pinfunction "VIO_11") (pintype "power_in"))
      (node (ref "U502") (pin "2") (pinfunction "VREFA_2") (pintype "power_in"))
      (node (ref "Y500") (pin "4") (pinfunction "VCC_4") (pintype "power_in"))
    )
    (net (code "44") (name "VCC3V3") (class "Default")
      (node (ref "C502") (pin "1") (pinfunction "1_1") (pintype "passive"))
      (node (ref "C503") (pin "1") (pinfunction "1_1") (pintype "passive"))
      (node (ref "C504") (pin "1") (pinfunction "1_1") (pintype "passive"))
      (node (ref "R501") (pin "2") (pinfunction "2_2") (pintype "passive"))
      (node (ref "R502") (pin "1") (pinfunction "1_1") (pintype "passive"))
      (node (ref "R503") (pin "1") (pinfunction "1_1") (pintype "passive"))
      (node (ref "R504") (pin "1") (pinfunction "1_1") (pintype "passive"))
      (node (ref "R505") (pin "1") (pinfunction "1_1") (pintype "passive"))
      (node (ref "R506") (pin "1") (pinfunction "1_1") (pintype "passive"))
      (node (ref "R507") (pin "1") (pinfunction "1_1") (pintype "passive"))
      (node (ref "R514") (pin "2") (pinfunction "2_2") (pintype "passive"))
      (node (ref "R515") (pin "2") (pinfunction "2_2") (pintype "passive"))
      (node (ref "R516") (pin "2") (pinfunction "2_2") (pintype "passive"))
      (node (ref "R517") (pin "2") (pinfunction "2_2") (pintype "passive"))
      (node (ref "R518") (pin "2") (pinfunction "2_2") (pintype "passive"))
      (node (ref "R519") (pin "2") (pinfunction "2_2") (pintype "passive"))
      (node (ref "U501") (pin "1") (pinfunction "VBAT_1") (pintype "power_in"))
    )
    (net (code "45") (name "unconnected-(ANT500-ANTENNA-PadANT)") (class "Default")
      (node (ref "ANT500") (pin "ANT") (pinfunction "ANTENNA_ANT") (pintype "passive+no_connect"))
    )
    (net (code "46") (name "unconnected-(U501-FMRFOUT-Pad28)") (class "Default")
      (node (ref "U501") (pin "28") (pinfunction "FMRFOUT_28") (pintype "output+no_connect"))
    )
    (net (code "47") (name "unconnected-(U501-FM_AUD_LOUT-Pad32)") (class "Default")
      (node (ref "U501") (pin "32") (pinfunction "FM_AUD_LOUT_32") (pintype "output+no_connect"))
    )
    (net (code "48") (name "unconnected-(U501-FM_AUD_ROUT-Pad31)") (class "Default")
      (node (ref "U501") (pin "31") (pinfunction "FM_AUD_ROUT_31") (pintype "output+no_connect"))
    )
    (net (code "49") (name "unconnected-(U501-FM_I2S_CLK-Pad23)") (class "Default")
      (node (ref "U501") (pin "23") (pinfunction "FM_I2S_CLK_23") (pintype "output+no_connect"))
    )
    (net (code "50") (name "unconnected-(U501-FM_I2S_DO-Pad25)") (class "Default")
      (node (ref "U501") (pin "25") (pinfunction "FM_I2S_DO_25") (pintype "output+no_connect"))
    )
    (net (code "51") (name "unconnected-(U501-FM_I2S_FSYNC-Pad9)") (class "Default")
      (node (ref "U501") (pin "9") (pinfunction "FM_I2S_FSYNC_9") (pintype "output+no_connect"))
    )
    (net (code "52") (name "unconnected-(U501-FM_IRQ-Pad20)") (class "Default")
      (node (ref "U501") (pin "20") (pinfunction "FM_IRQ_20") (pintype "output+no_connect"))
    )
    (net (code "53") (name "unconnected-(U501-FM_SCL-Pad22)") (class "Default")
      (node (ref "U501") (pin "22") (pinfunction "FM_SCL_22") (pintype "output+no_connect"))
    )
    (net (code "54") (name "unconnected-(U501-FM_SDA-Pad21)") (class "Default")
      (node (ref "U501") (pin "21") (pinfunction "FM_SDA_21") (pintype "output+no_connect"))
    )
    (net (code "55") (name "unconnected-(U502-A6-Pad8)") (class "Default")
      (node (ref "U502") (pin "8") (pinfunction "A6_8") (pintype "bidirectional+no_connect"))
    )
    (net (code "56") (name "unconnected-(U502-B6-Pad9)") (class "Default")
      (node (ref "U502") (pin "9") (pinfunction "B6_9") (pintype "bidirectional+no_connect"))
    )
    (net (code "57") (name "unconnected-(Y500-TRI-Pad1)") (class "Default")
      (node (ref "Y500") (pin "1") (pinfunction "TRI_1") (pintype "passive+no_connect"))
    )
  )
)
